# LVDS.net
KiCad netlist of a schematic drawn in EAGLE
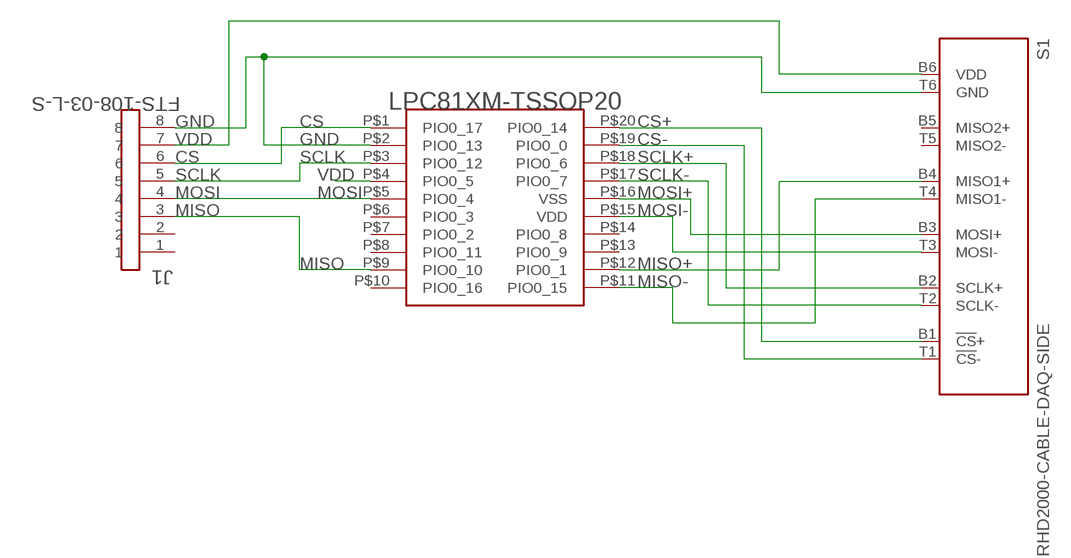
[diagram p0: schematic, sheet 1]

(export (version "E")
  (design (tool "Eeschema 10.0.6"))
  (components
    (comp (ref "J1")
      (value "FTS-108-03-L-S")
      (footprint "eagle-import:SAMTEC_FTS-108-03-S")
      (fields (field (name "MPN") "FTS-108-03-L-D"))
      (libsource (lib "eagle-import") (part "FTS-108-03-L-S"))
    )
    (comp (ref "LVDS")
      (value "LPC81XM_TSSOP20")
      (footprint "eagle-import:TSSOP20")
      (libsource (lib "eagle-import") (part "LPC81XM_TSSOP20"))
    )
    (comp (ref "S1")
      (value "RHD2000-CABLE-DAQ-SIDE")
      (footprint "eagle-import:OMNETICS_PZN-12-AA")
      (libsource (lib "eagle-import") (part "RHD2000-CABLE-DAQ-SIDE"))
    )
  )
  (nets
    (net (code "1") (name "/CS") (class "Default")
      (node (ref "J1") (pin "6") (pinfunction "6_6") (pintype "passive"))
      (node (ref "LVDS") (pin "P$1") (pinfunction "PIO0_17_P$1") (pintype "bidirectional"))
    )
    (net (code "2") (name "/CS+") (class "Default")
      (node (ref "LVDS") (pin "P$20") (pinfunction "PIO0_14_P$20") (pintype "bidirectional"))
      (node (ref "S1") (pin "B1") (pinfunction "~{CS}+_B1") (pintype "bidirectional"))
    )
    (net (code "3") (name "/CS-") (class "Default")
      (node (ref "LVDS") (pin "P$19") (pinfunction "PIO0_0_P$19") (pintype "bidirectional"))
      (node (ref "S1") (pin "T1") (pinfunction "~{CS}-_T1") (pintype "bidirectional"))
    )
    (net (code "4") (name "/GND") (class "Default")
      (node (ref "J1") (pin "8") (pinfunction "8_8") (pintype "passive"))
      (node (ref "LVDS") (pin "P$2") (pinfunction "PIO0_13_P$2") (pintype "bidirectional"))
      (node (ref "S1") (pin "T6") (pinfunction "GND_T6") (pintype "power_in"))
    )
    (net (code "5") (name "/MISO") (class "Default")
      (node (ref "J1") (pin "3") (pinfunction "3_3") (pintype "passive"))
      (node (ref "LVDS") (pin "P$9") (pinfunction "PIO0_10_P$9") (pintype "bidirectional"))
    )
    (net (code "6") (name "/MISO+") (class "Default")
      (node (ref "LVDS") (pin "P$12") (pinfunction "PIO0_1_P$12") (pintype "bidirectional"))
      (node (ref "S1") (pin "B4") (pinfunction "MISO1+_B4") (pintype "bidirectional"))
    )
    (net (code "7") (name "/MISO-") (class "Default")
      (node (ref "LVDS") (pin "P$11") (pinfunction "PIO0_15_P$11") (pintype "bidirectional"))
      (node (ref "S1") (pin "T4") (pinfunction "MISO1-_T4") (pintype "bidirectional"))
    )
    (net (code "8") (name "/MOSI") (class "Default")
      (node (ref "J1") (pin "4") (pinfunction "4_4") (pintype "passive"))
      (node (ref "LVDS") (pin "P$5") (pinfunction "PIO0_4_P$5") (pintype "bidirectional"))
    )
    (net (code "9") (name "/MOSI+") (class "Default")
      (node (ref "LVDS") (pin "P$16") (pinfunction "VSS_P$16") (pintype "bidirectional"))
      (node (ref "S1") (pin "B3") (pinfunction "MOSI+_B3") (pintype "bidirectional"))
    )
    (net (code "10") (name "/MOSI-") (class "Default")
      (node (ref "LVDS") (pin "P$15") (pinfunction "VDD_P$15") (pintype "bidirectional"))
      (node (ref "S1") (pin "T3") (pinfunction "MOSI-_T3") (pintype "bidirectional"))
    )
    (net (code "11") (name "/SCLK") (class "Default")
      (node (ref "J1") (pin "5") (pinfunction "5_5") (pintype "passive"))
      (node (ref "LVDS") (pin "P$3") (pinfunction "PIO0_12_P$3") (pintype "bidirectional"))
    )
    (net (code "12") (name "/SCLK+") (class "Default")
      (node (ref "LVDS") (pin "P$18") (pinfunction "PIO0_6_P$18") (pintype "bidirectional"))
      (node (ref "S1") (pin "B2") (pinfunction "SCLK+_B2") (pintype "bidirectional"))
    )
    (net (code "13") (name "/SCLK-") (class "Default")
      (node (ref "LVDS") (pin "P$17") (pinfunction "PIO0_7_P$17") (pintype "bidirectional"))
      (node (ref "S1") (pin "T2") (pinfunction "SCLK-_T2") (pintype "bidirectional"))
    )
    (net (code "14") (name "/VDD") (class "Default")
      (node (ref "J1") (pin "7") (pinfunction "7_7") (pintype "passive"))
      (node (ref "LVDS") (pin "P$4") (pinfunction "PIO0_5_P$4") (pintype "bidirectional"))
      (node (ref "S1") (pin "B6") (pinfunction "VDD_B6") (pintype "bidirectional"))
    )
    (net (code "15") (name "unconnected-(J1-Pad1)") (class "Default")
      (node (ref "J1") (pin "1") (pinfunction "1_1") (pintype "passive"))
    )
    (net (code "16") (name "unconnected-(J1-Pad2)") (class "Default")
      (node (ref "J1") (pin "2") (pinfunction "2_2") (pintype "passive"))
    )
    (net (code "17") (name "unconnected-(LVDS-PIO0_2-PadP$7)") (class "Default")
      (node (ref "LVDS") (pin "P$7") (pinfunction "PIO0_2_P$7") (pintype "bidirectional"))
    )
    (net (code "18") (name "unconnected-(LVDS-PIO0_3-PadP$6)") (class "Default")
      (node (ref "LVDS") (pin "P$6") (pinfunction "PIO0_3_P$6") (pintype "bidirectional"))
    )
    (net (code "19") (name "unconnected-(LVDS-PIO0_8-PadP$14)") (class "Default")
      (node (ref "LVDS") (pin "P$14") (pinfunction "PIO0_8_P$14") (pintype "bidirectional"))
    )
    (net (code "20") (name "unconnected-(LVDS-PIO0_9-PadP$13)") (class "Default")
      (node (ref "LVDS") (pin "P$13") (pinfunction "PIO0_9_P$13") (pintype "bidirectional"))
    )
    (net (code "21") (name "unconnected-(LVDS-PIO0_11-PadP$8)") (class "Default")
      (node (ref "LVDS") (pin "P$8") (pinfunction "PIO0_11_P$8") (pintype "bidirectional"))
    )
    (net (code "22") (name "unconnected-(LVDS-PIO0_16-PadP$10)") (class "Default")
      (node (ref "LVDS") (pin "P$10") (pinfunction "PIO0_16_P$10") (pintype "bidirectional"))
    )
    (net (code "23") (name "unconnected-(S1-MISO2+-PadB5)") (class "Default")
      (node (ref "S1") (pin "B5") (pinfunction "MISO2+_B5") (pintype "bidirectional"))
    )
    (net (code "24") (name "unconnected-(S1-MISO2--PadT5)") (class "Default")
      (node (ref "S1") (pin "T5") (pinfunction "MISO2-_T5") (pintype "bidirectional"))
    )
  )
)
